# Power.net
KiCad netlist of a schematic drawn in Altium Designer
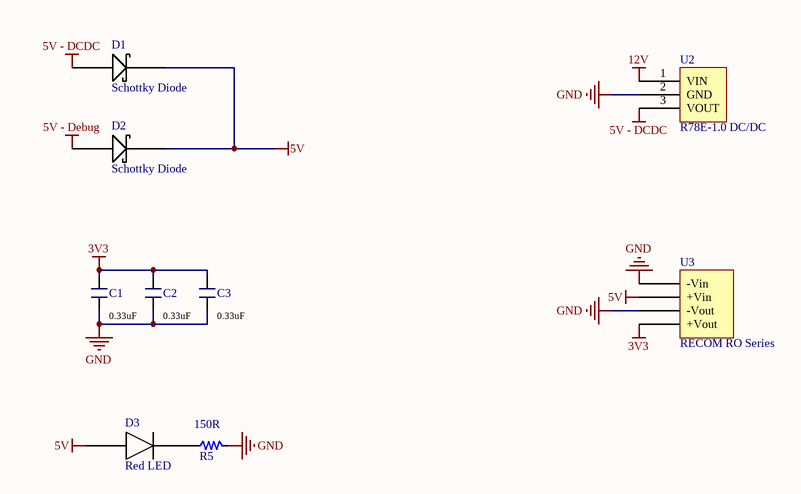
[diagram p0: Power.SchDoc]

(export (version "E")
  (design (tool "Eeschema 10.0.6"))
  (components
    (comp (ref "C1")
      (value "SCH_GENERIC_CAPACITOR_0603")
      (footprint "PCB_GENERIC_SMD_0603")
      (description "Generic SMD capacitor 0603")
      (fields (field (name "CAPACITANCE") "0.33uF"))
      (libsource (lib "Capacitors") (part "SCH_GENERIC_CAPACITOR_0603"))
    )
    (comp (ref "C2")
      (value "SCH_GENERIC_CAPACITOR_0603")
      (footprint "PCB_GENERIC_SMD_0603")
      (description "Generic SMD capacitor 0603")
      (fields (field (name "TOLERANCE") "*%") (field (name "CAPACITANCE") "0.33uF"))
      (libsource (lib "Capacitors") (part "SCH_GENERIC_CAPACITOR_0603"))
    )
    (comp (ref "C3")
      (value "SCH_GENERIC_CAPACITOR_0603")
      (footprint "PCB_GENERIC_SMD_0603")
      (description "Generic SMD capacitor 0603")
      (fields (field (name "TOLERANCE") "*%") (field (name "CAPACITANCE") "0.33uF"))
      (libsource (lib "Capacitors") (part "SCH_GENERIC_CAPACITOR_0603"))
    )
    (comp (ref "D1")
      (value "Schottky Diode")
      (footprint "ON Semi Schottky Diode - MBRM110LT1G")
      (libsource (lib "ON Semi Schottky Diode - MBRM110LT1G") (part "ON Semi Schottky Diode - MBRM110LT1G"))
    )
    (comp (ref "D2")
      (value "Schottky Diode")
      (footprint "ON Semi Schottky Diode - MBRM110LT1G")
      (libsource (lib "ON Semi Schottky Diode - MBRM110LT1G") (part "ON Semi Schottky Diode - MBRM110LT1G"))
    )
    (comp (ref "D3")
      (value "Red LED")
      (footprint "SMD_0603_LED")
      (libsource (lib "SMD_0603_LED") (part "SMD_0603_LED"))
    )
    (comp (ref "R5")
      (value "SCH_GENERIC_RESISTOR_0603")
      (footprint "Generic 0603 Resistor:PCB_GENERIC_SMD_0603")
      (description "Generic SMD resistor 0603")
      (fields (field (name "RESISTANCE") "150R"))
      (libsource (lib "SCH_GENERIC_RESISTOR_0603") (part "SCH_GENERIC_RESISTOR_0603"))
    )
    (comp (ref "U2")
      (value "R78E-1.0 DC/DC")
      (footprint "R78-1.0")
      (libsource (lib "R78E-1.0_DCDC_SCH") (part "R78E-1.0"))
    )
    (comp (ref "U3")
      (value "RECOM RO Series")
      (footprint "Recom RO Series 1W DCDC:RECOM RO Series 1W DCDC")
      (libsource (lib "RECOM RO Series 1W DCDC") (part "RECOM RO Series DCDC Converter"))
    )
  )
  (nets
    (net (code "1") (name "3V3") (class "Default")
      (node (ref "C1") (pin "2") (pinfunction "2_2") (pintype "passive"))
      (node (ref "C2") (pin "2") (pinfunction "2_2") (pintype "passive"))
      (node (ref "C3") (pin "2") (pinfunction "2_2") (pintype "passive"))
      (node (ref "U3") (pin "4") (pinfunction "+Vout_4") (pintype "passive"))
    )
    (net (code "2") (name "5V") (class "Default")
      (node (ref "D1") (pin "1") (pinfunction "1_1") (pintype "passive"))
      (node (ref "D2") (pin "1") (pinfunction "1_1") (pintype "passive"))
      (node (ref "D3") (pin "1") (pinfunction "1_1") (pintype "passive"))
      (node (ref "U3") (pin "2") (pinfunction "+Vin_2") (pintype "passive"))
    )
    (net (code "3") (name "5V - DCDC") (class "Default")
      (node (ref "D1") (pin "2") (pinfunction "2_2") (pintype "passive"))
      (node (ref "U2") (pin "3") (pinfunction "VOUT_3") (pintype "passive"))
    )
    (net (code "4") (name "5V - Debug") (class "Default")
      (node (ref "D2") (pin "2") (pinfunction "2_2") (pintype "passive"))
    )
    (net (code "5") (name "12V") (class "Default")
      (node (ref "U2") (pin "1") (pinfunction "VIN_1") (pintype "passive"))
    )
    (net (code "6") (name "GND") (class "Default")
      (node (ref "C1") (pin "1") (pinfunction "1_1") (pintype "passive"))
      (node (ref "C2") (pin "1") (pinfunction "1_1") (pintype "passive"))
      (node (ref "C3") (pin "1") (pinfunction "1_1") (pintype "passive"))
      (node (ref "R5") (pin "2") (pinfunction "2_2") (pintype "passive"))
      (node (ref "U2") (pin "2") (pinfunction "GND_2") (pintype "passive"))
      (node (ref "U3") (pin "1") (pinfunction "-Vin_1") (pintype "passive"))
      (node (ref "U3") (pin "3") (pinfunction "-Vout_3") (pintype "passive"))
    )
    (net (code "7") (name "Net-(D3-Pad2)") (class "Default")
      (node (ref "D3") (pin "2") (pinfunction "2_2") (pintype "passive"))
      (node (ref "R5") (pin "1") (pinfunction "1_1") (pintype "passive"))
    )
  )
)
